# final.net
KiCad netlist of a schematic drawn in EAGLE
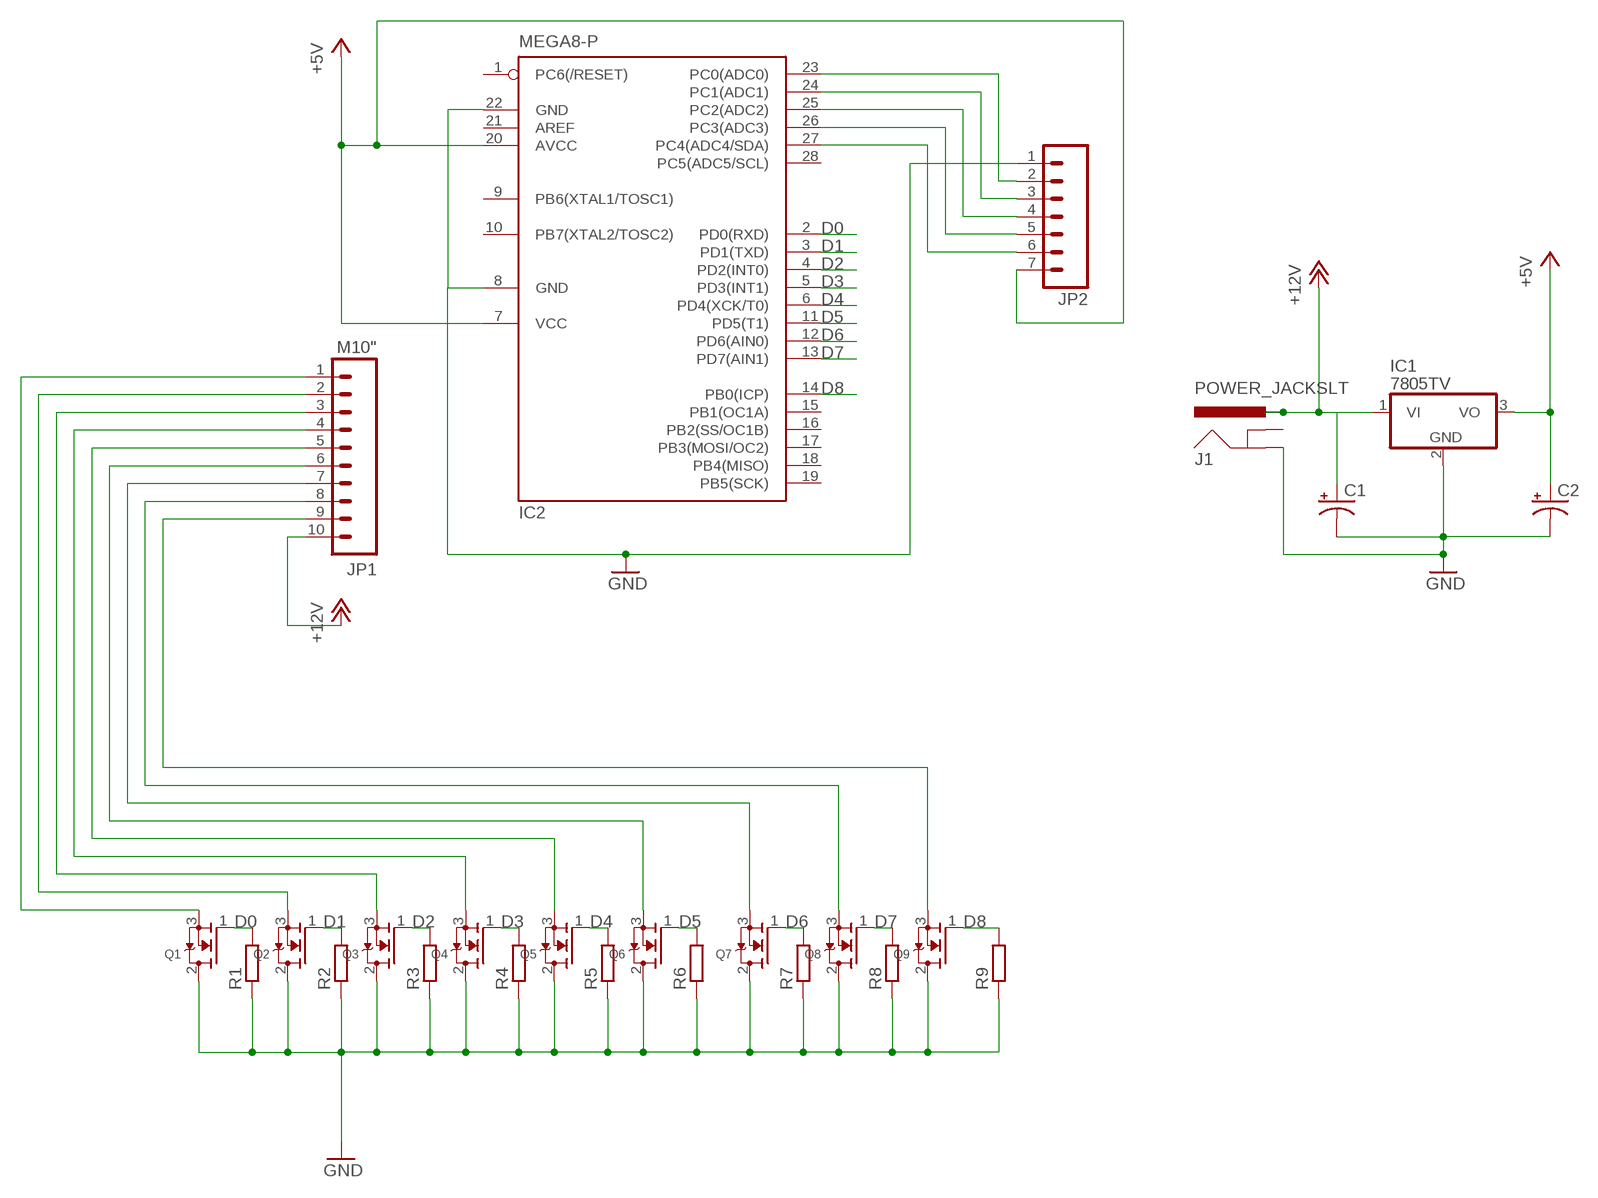
[diagram p0: schematic, sheet 1]

(export (version "E")
  (design (tool "Eeschema 10.0.6"))
  (components
    (comp (ref "C1")
      (value "CAP_POLPTH1")
      (footprint "eagle-import:CPOL-RADIAL-100UF-25V")
      (libsource (lib "eagle-import") (part "CAP_POLPTH1"))
    )
    (comp (ref "C2")
      (value "CAP_POLPTH1")
      (footprint "eagle-import:CPOL-RADIAL-100UF-25V")
      (libsource (lib "eagle-import") (part "CAP_POLPTH1"))
    )
    (comp (ref "IC1")
      (value "7805TV")
      (footprint "eagle-import:TO220V")
      (libsource (lib "eagle-import") (part "78TV05"))
    )
    (comp (ref "IC2")
      (value "MEGA8-P")
      (footprint "eagle-import:DIL28-3")
      (libsource (lib "eagle-import") (part "MEGA8-P"))
    )
    (comp (ref "J1")
      (value "POWER_JACKSLT")
      (footprint "eagle-import:POWER_JACK_SLOT")
      (libsource (lib "eagle-import") (part "POWER_JACKSLT"))
    )
    (comp (ref "JP1")
      (value "M10\"")
      (footprint "eagle-import:1X10")
      (libsource (lib "eagle-import") (part "M10{dblquote}"))
    )
    (comp (ref "JP2")
      (value "M07")
      (footprint "eagle-import:1X07")
      (libsource (lib "eagle-import") (part "M07"))
    )
    (comp (ref "Q1")
      (value "MOSFET-NGDS_TO220V")
      (footprint "eagle-import:TO220V")
      (libsource (lib "eagle-import") (part "MOSFET-NGDS_TO220V"))
    )
    (comp (ref "Q2")
      (value "MOSFET-NGDS_TO220V")
      (footprint "eagle-import:TO220V")
      (libsource (lib "eagle-import") (part "MOSFET-NGDS_TO220V"))
    )
    (comp (ref "Q3")
      (value "MOSFET-NGDS_TO220V")
      (footprint "eagle-import:TO220V")
      (libsource (lib "eagle-import") (part "MOSFET-NGDS_TO220V"))
    )
    (comp (ref "Q4")
      (value "MOSFET-NGDS_TO220V")
      (footprint "eagle-import:TO220V")
      (libsource (lib "eagle-import") (part "MOSFET-NGDS_TO220V"))
    )
    (comp (ref "Q5")
      (value "MOSFET-NGDS_TO220V")
      (footprint "eagle-import:TO220V")
      (libsource (lib "eagle-import") (part "MOSFET-NGDS_TO220V"))
    )
    (comp (ref "Q6")
      (value "MOSFET-NGDS_TO220V")
      (footprint "eagle-import:TO220V")
      (libsource (lib "eagle-import") (part "MOSFET-NGDS_TO220V"))
    )
    (comp (ref "Q7")
      (value "MOSFET-NGDS_TO220V")
      (footprint "eagle-import:TO220V")
      (libsource (lib "eagle-import") (part "MOSFET-NGDS_TO220V"))
    )
    (comp (ref "Q8")
      (value "MOSFET-NGDS_TO220V")
      (footprint "eagle-import:TO220V")
      (libsource (lib "eagle-import") (part "MOSFET-NGDS_TO220V"))
    )
    (comp (ref "Q9")
      (value "MOSFET-NGDS_TO220V")
      (footprint "eagle-import:TO220V")
      (libsource (lib "eagle-import") (part "MOSFET-NGDS_TO220V"))
    )
    (comp (ref "R1")
      (value "R-EU_M0805")
      (footprint "eagle-import:M0805")
      (libsource (lib "eagle-import") (part "R-EU_M0805"))
    )
    (comp (ref "R2")
      (value "R-EU_M0805")
      (footprint "eagle-import:M0805")
      (libsource (lib "eagle-import") (part "R-EU_M0805"))
    )
    (comp (ref "R3")
      (value "R-EU_M0805")
      (footprint "eagle-import:M0805")
      (libsource (lib "eagle-import") (part "R-EU_M0805"))
    )
    (comp (ref "R4")
      (value "R-EU_M0805")
      (footprint "eagle-import:M0805")
      (libsource (lib "eagle-import") (part "R-EU_M0805"))
    )
    (comp (ref "R5")
      (value "R-EU_M0805")
      (footprint "eagle-import:M0805")
      (libsource (lib "eagle-import") (part "R-EU_M0805"))
    )
    (comp (ref "R6")
      (value "R-EU_M0805")
      (footprint "eagle-import:M0805")
      (libsource (lib "eagle-import") (part "R-EU_M0805"))
    )
    (comp (ref "R7")
      (value "R-EU_M0805")
      (footprint "eagle-import:M0805")
      (libsource (lib "eagle-import") (part "R-EU_M0805"))
    )
    (comp (ref "R8")
      (value "R-EU_M0805")
      (footprint "eagle-import:M0805")
      (libsource (lib "eagle-import") (part "R-EU_M0805"))
    )
    (comp (ref "R9")
      (value "R-EU_M0805")
      (footprint "eagle-import:M0805")
      (libsource (lib "eagle-import") (part "R-EU_M0805"))
    )
  )
  (nets
    (net (code "1") (name "+5V") (class "Default")
      (node (ref "C2") (pin "1") (pinfunction "+_1") (pintype "passive"))
      (node (ref "IC1") (pin "3") (pinfunction "VO_3") (pintype "passive"))
      (node (ref "IC2") (pin "20") (pinfunction "AVCC_20") (pintype "power_in"))
      (node (ref "IC2") (pin "7") (pinfunction "VCC_7") (pintype "power_in"))
      (node (ref "JP2") (pin "7") (pinfunction "7_7") (pintype "passive"))
    )
    (net (code "2") (name "+12V") (class "Default")
      (node (ref "C1") (pin "1") (pinfunction "+_1") (pintype "passive"))
      (node (ref "IC1") (pin "1") (pinfunction "VI_1") (pintype "input"))
      (node (ref "J1") (pin "PWR") (pinfunction "PWR_PWR") (pintype "bidirectional"))
      (node (ref "JP1") (pin "10") (pinfunction "10_10") (pintype "passive"))
    )
    (net (code "3") (name "/D0") (class "Default")
      (node (ref "IC2") (pin "2") (pinfunction "PD0(RXD)_2") (pintype "bidirectional"))
      (node (ref "Q1") (pin "1") (pinfunction "G_1") (pintype "bidirectional"))
      (node (ref "R1") (pin "2") (pinfunction "2_2") (pintype "passive"))
    )
    (net (code "4") (name "/D1") (class "Default")
      (node (ref "IC2") (pin "3") (pinfunction "PD1(TXD)_3") (pintype "bidirectional"))
      (node (ref "Q2") (pin "1") (pinfunction "G_1") (pintype "bidirectional"))
      (node (ref "R2") (pin "2") (pinfunction "2_2") (pintype "passive"))
    )
    (net (code "5") (name "/D2") (class "Default")
      (node (ref "IC2") (pin "4") (pinfunction "PD2(INT0)_4") (pintype "bidirectional"))
      (node (ref "Q3") (pin "1") (pinfunction "G_1") (pintype "bidirectional"))
      (node (ref "R3") (pin "2") (pinfunction "2_2") (pintype "passive"))
    )
    (net (code "6") (name "/D3") (class "Default")
      (node (ref "IC2") (pin "5") (pinfunction "PD3(INT1)_5") (pintype "bidirectional"))
      (node (ref "Q4") (pin "1") (pinfunction "G_1") (pintype "bidirectional"))
      (node (ref "R4") (pin "2") (pinfunction "2_2") (pintype "passive"))
    )
    (net (code "7") (name "/D4") (class "Default")
      (node (ref "IC2") (pin "6") (pinfunction "PD4(XCK/T0)_6") (pintype "bidirectional"))
      (node (ref "Q5") (pin "1") (pinfunction "G_1") (pintype "bidirectional"))
      (node (ref "R5") (pin "2") (pinfunction "2_2") (pintype "passive"))
    )
    (net (code "8") (name "/D5") (class "Default")
      (node (ref "IC2") (pin "11") (pinfunction "PD5(T1)_11") (pintype "bidirectional"))
      (node (ref "Q6") (pin "1") (pinfunction "G_1") (pintype "bidirectional"))
      (node (ref "R6") (pin "2") (pinfunction "2_2") (pintype "passive"))
    )
    (net (code "9") (name "/D6") (class "Default")
      (node (ref "IC2") (pin "12") (pinfunction "PD6(AIN0)_12") (pintype "bidirectional"))
      (node (ref "Q7") (pin "1") (pinfunction "G_1") (pintype "bidirectional"))
      (node (ref "R7") (pin "2") (pinfunction "2_2") (pintype "passive"))
    )
    (net (code "10") (name "/D7") (class "Default")
      (node (ref "IC2") (pin "13") (pinfunction "PD7(AIN1)_13") (pintype "bidirectional"))
      (node (ref "Q8") (pin "1") (pinfunction "G_1") (pintype "bidirectional"))
      (node (ref "R8") (pin "2") (pinfunction "2_2") (pintype "passive"))
    )
    (net (code "11") (name "/D8") (class "Default")
      (node (ref "IC2") (pin "14") (pinfunction "PB0(ICP)_14") (pintype "bidirectional"))
      (node (ref "Q9") (pin "1") (pinfunction "G_1") (pintype "bidirectional"))
      (node (ref "R9") (pin "2") (pinfunction "2_2") (pintype "passive"))
    )
    (net (code "12") (name "GND") (class "Default")
      (node (ref "C1") (pin "2") (pinfunction "-_2") (pintype "passive"))
      (node (ref "C2") (pin "2") (pinfunction "-_2") (pintype "passive"))
      (node (ref "IC1") (pin "2") (pinfunction "GND_2") (pintype "passive"))
      (node (ref "IC2") (pin "22") (pinfunction "GND_22") (pintype "power_in"))
      (node (ref "IC2") (pin "8") (pinfunction "GND_8") (pintype "power_in"))
      (node (ref "J1") (pin "GND@2") (pinfunction "GND_GND@2") (pintype "bidirectional"))
      (node (ref "JP2") (pin "1") (pinfunction "1_1") (pintype "passive"))
      (node (ref "Q1") (pin "2") (pinfunction "D_2") (pintype "bidirectional"))
      (node (ref "Q2") (pin "2") (pinfunction "D_2") (pintype "bidirectional"))
      (node (ref "Q3") (pin "2") (pinfunction "D_2") (pintype "bidirectional"))
      (node (ref "Q4") (pin "2") (pinfunction "D_2") (pintype "bidirectional"))
      (node (ref "Q5") (pin "2") (pinfunction "D_2") (pintype "bidirectional"))
      (node (ref "Q6") (pin "2") (pinfunction "D_2") (pintype "bidirectional"))
      (node (ref "Q7") (pin "2") (pinfunction "D_2") (pintype "bidirectional"))
      (node (ref "Q8") (pin "2") (pinfunction "D_2") (pintype "bidirectional"))
      (node (ref "Q9") (pin "2") (pinfunction "D_2") (pintype "bidirectional"))
      (node (ref "R1") (pin "1") (pinfunction "1_1") (pintype "passive"))
      (node (ref "R2") (pin "1") (pinfunction "1_1") (pintype "passive"))
      (node (ref "R3") (pin "1") (pinfunction "1_1") (pintype "passive"))
      (node (ref "R4") (pin "1") (pinfunction "1_1") (pintype "passive"))
      (node (ref "R5") (pin "1") (pinfunction "1_1") (pintype "passive"))
      (node (ref "R6") (pin "1") (pinfunction "1_1") (pintype "passive"))
      (node (ref "R7") (pin "1") (pinfunction "1_1") (pintype "passive"))
      (node (ref "R8") (pin "1") (pinfunction "1_1") (pintype "passive"))
      (node (ref "R9") (pin "1") (pinfunction "1_1") (pintype "passive"))
    )
    (net (code "13") (name "Net-(IC2-PC0(ADC0))") (class "Default")
      (node (ref "IC2") (pin "23") (pinfunction "PC0(ADC0)_23") (pintype "bidirectional"))
      (node (ref "JP2") (pin "2") (pinfunction "2_2") (pintype "passive"))
    )
    (net (code "14") (name "Net-(IC2-PC1(ADC1))") (class "Default")
      (node (ref "IC2") (pin "24") (pinfunction "PC1(ADC1)_24") (pintype "bidirectional"))
      (node (ref "JP2") (pin "3") (pinfunction "3_3") (pintype "passive"))
    )
    (net (code "15") (name "Net-(IC2-PC2(ADC2))") (class "Default")
      (node (ref "IC2") (pin "25") (pinfunction "PC2(ADC2)_25") (pintype "bidirectional"))
      (node (ref "JP2") (pin "4") (pinfunction "4_4") (pintype "passive"))
    )
    (net (code "16") (name "Net-(IC2-PC3(ADC3))") (class "Default")
      (node (ref "IC2") (pin "26") (pinfunction "PC3(ADC3)_26") (pintype "bidirectional"))
      (node (ref "JP2") (pin "5") (pinfunction "5_5") (pintype "passive"))
    )
    (net (code "17") (name "Net-(IC2-PC4(ADC4{slash}SDA))") (class "Default")
      (node (ref "IC2") (pin "27") (pinfunction "PC4(ADC4/SDA)_27") (pintype "bidirectional"))
      (node (ref "JP2") (pin "6") (pinfunction "6_6") (pintype "passive"))
    )
    (net (code "18") (name "Net-(Q1-S)") (class "Default")
      (node (ref "JP1") (pin "1") (pinfunction "1_1") (pintype "passive"))
      (node (ref "Q1") (pin "3") (pinfunction "S_3") (pintype "bidirectional"))
    )
    (net (code "19") (name "Net-(Q2-S)") (class "Default")
      (node (ref "JP1") (pin "2") (pinfunction "2_2") (pintype "passive"))
      (node (ref "Q2") (pin "3") (pinfunction "S_3") (pintype "bidirectional"))
    )
    (net (code "20") (name "Net-(Q3-S)") (class "Default")
      (node (ref "JP1") (pin "3") (pinfunction "3_3") (pintype "passive"))
      (node (ref "Q3") (pin "3") (pinfunction "S_3") (pintype "bidirectional"))
    )
    (net (code "21") (name "Net-(Q4-S)") (class "Default")
      (node (ref "JP1") (pin "4") (pinfunction "4_4") (pintype "passive"))
      (node (ref "Q4") (pin "3") (pinfunction "S_3") (pintype "bidirectional"))
    )
    (net (code "22") (name "Net-(Q5-S)") (class "Default")
      (node (ref "JP1") (pin "5") (pinfunction "5_5") (pintype "passive"))
      (node (ref "Q5") (pin "3") (pinfunction "S_3") (pintype "bidirectional"))
    )
    (net (code "23") (name "Net-(Q6-S)") (class "Default")
      (node (ref "JP1") (pin "6") (pinfunction "6_6") (pintype "passive"))
      (node (ref "Q6") (pin "3") (pinfunction "S_3") (pintype "bidirectional"))
    )
    (net (code "24") (name "Net-(Q7-S)") (class "Default")
      (node (ref "JP1") (pin "7") (pinfunction "7_7") (pintype "passive"))
      (node (ref "Q7") (pin "3") (pinfunction "S_3") (pintype "bidirectional"))
    )
    (net (code "25") (name "Net-(Q8-S)") (class "Default")
      (node (ref "JP1") (pin "8") (pinfunction "8_8") (pintype "passive"))
      (node (ref "Q8") (pin "3") (pinfunction "S_3") (pintype "bidirectional"))
    )
    (net (code "26") (name "Net-(Q9-S)") (class "Default")
      (node (ref "JP1") (pin "9") (pinfunction "9_9") (pintype "passive"))
      (node (ref "Q9") (pin "3") (pinfunction "S_3") (pintype "bidirectional"))
    )
    (net (code "27") (name "unconnected-(IC2-AREF-Pad21)") (class "Default")
      (node (ref "IC2") (pin "21") (pinfunction "AREF_21") (pintype "passive"))
    )
    (net (code "28") (name "unconnected-(IC2-PB1(OC1A)-Pad15)") (class "Default")
      (node (ref "IC2") (pin "15") (pinfunction "PB1(OC1A)_15") (pintype "bidirectional"))
    )
    (net (code "29") (name "unconnected-(IC2-PB2(SS{slash}OC1B)-Pad16)") (class "Default")
      (node (ref "IC2") (pin "16") (pinfunction "PB2(SS/OC1B)_16") (pintype "bidirectional"))
    )
    (net (code "30") (name "unconnected-(IC2-PB3(MOSI{slash}OC2)-Pad17)") (class "Default")
      (node (ref "IC2") (pin "17") (pinfunction "PB3(MOSI/OC2)_17") (pintype "bidirectional"))
    )
    (net (code "31") (name "unconnected-(IC2-PB4(MISO)-Pad18)") (class "Default")
      (node (ref "IC2") (pin "18") (pinfunction "PB4(MISO)_18") (pintype "bidirectional"))
    )
    (net (code "32") (name "unconnected-(IC2-PB5(SCK)-Pad19)") (class "Default")
      (node (ref "IC2") (pin "19") (pinfunction "PB5(SCK)_19") (pintype "bidirectional"))
    )
    (net (code "33") (name "unconnected-(IC2-PB6(XTAL1{slash}TOSC1)-Pad9)") (class "Default")
      (node (ref "IC2") (pin "9") (pinfunction "PB6(XTAL1/TOSC1)_9") (pintype "bidirectional"))
    )
    (net (code "34") (name "unconnected-(IC2-PB7(XTAL2{slash}TOSC2)-Pad10)") (class "Default")
      (node (ref "IC2") (pin "10") (pinfunction "PB7(XTAL2/TOSC2)_10") (pintype "bidirectional"))
    )
    (net (code "35") (name "unconnected-(IC2-PC5(ADC5{slash}SCL)-Pad28)") (class "Default")
      (node (ref "IC2") (pin "28") (pinfunction "PC5(ADC5/SCL)_28") (pintype "bidirectional"))
    )
    (net (code "36") (name "unconnected-(IC2-PC6({slash}RESET)-Pad1)") (class "Default")
      (node (ref "IC2") (pin "1") (pinfunction "PC6(/RESET)_1") (pintype "bidirectional"))
    )
    (net (code "37") (name "unconnected-(J1-GNDBREAK-PadGND@1)") (class "Default")
      (node (ref "J1") (pin "GND@1") (pinfunction "GNDBREAK_GND@1") (pintype "bidirectional"))
    )
  )
)
